# BatteryV8.net
KiCad netlist of a schematic drawn in EAGLE
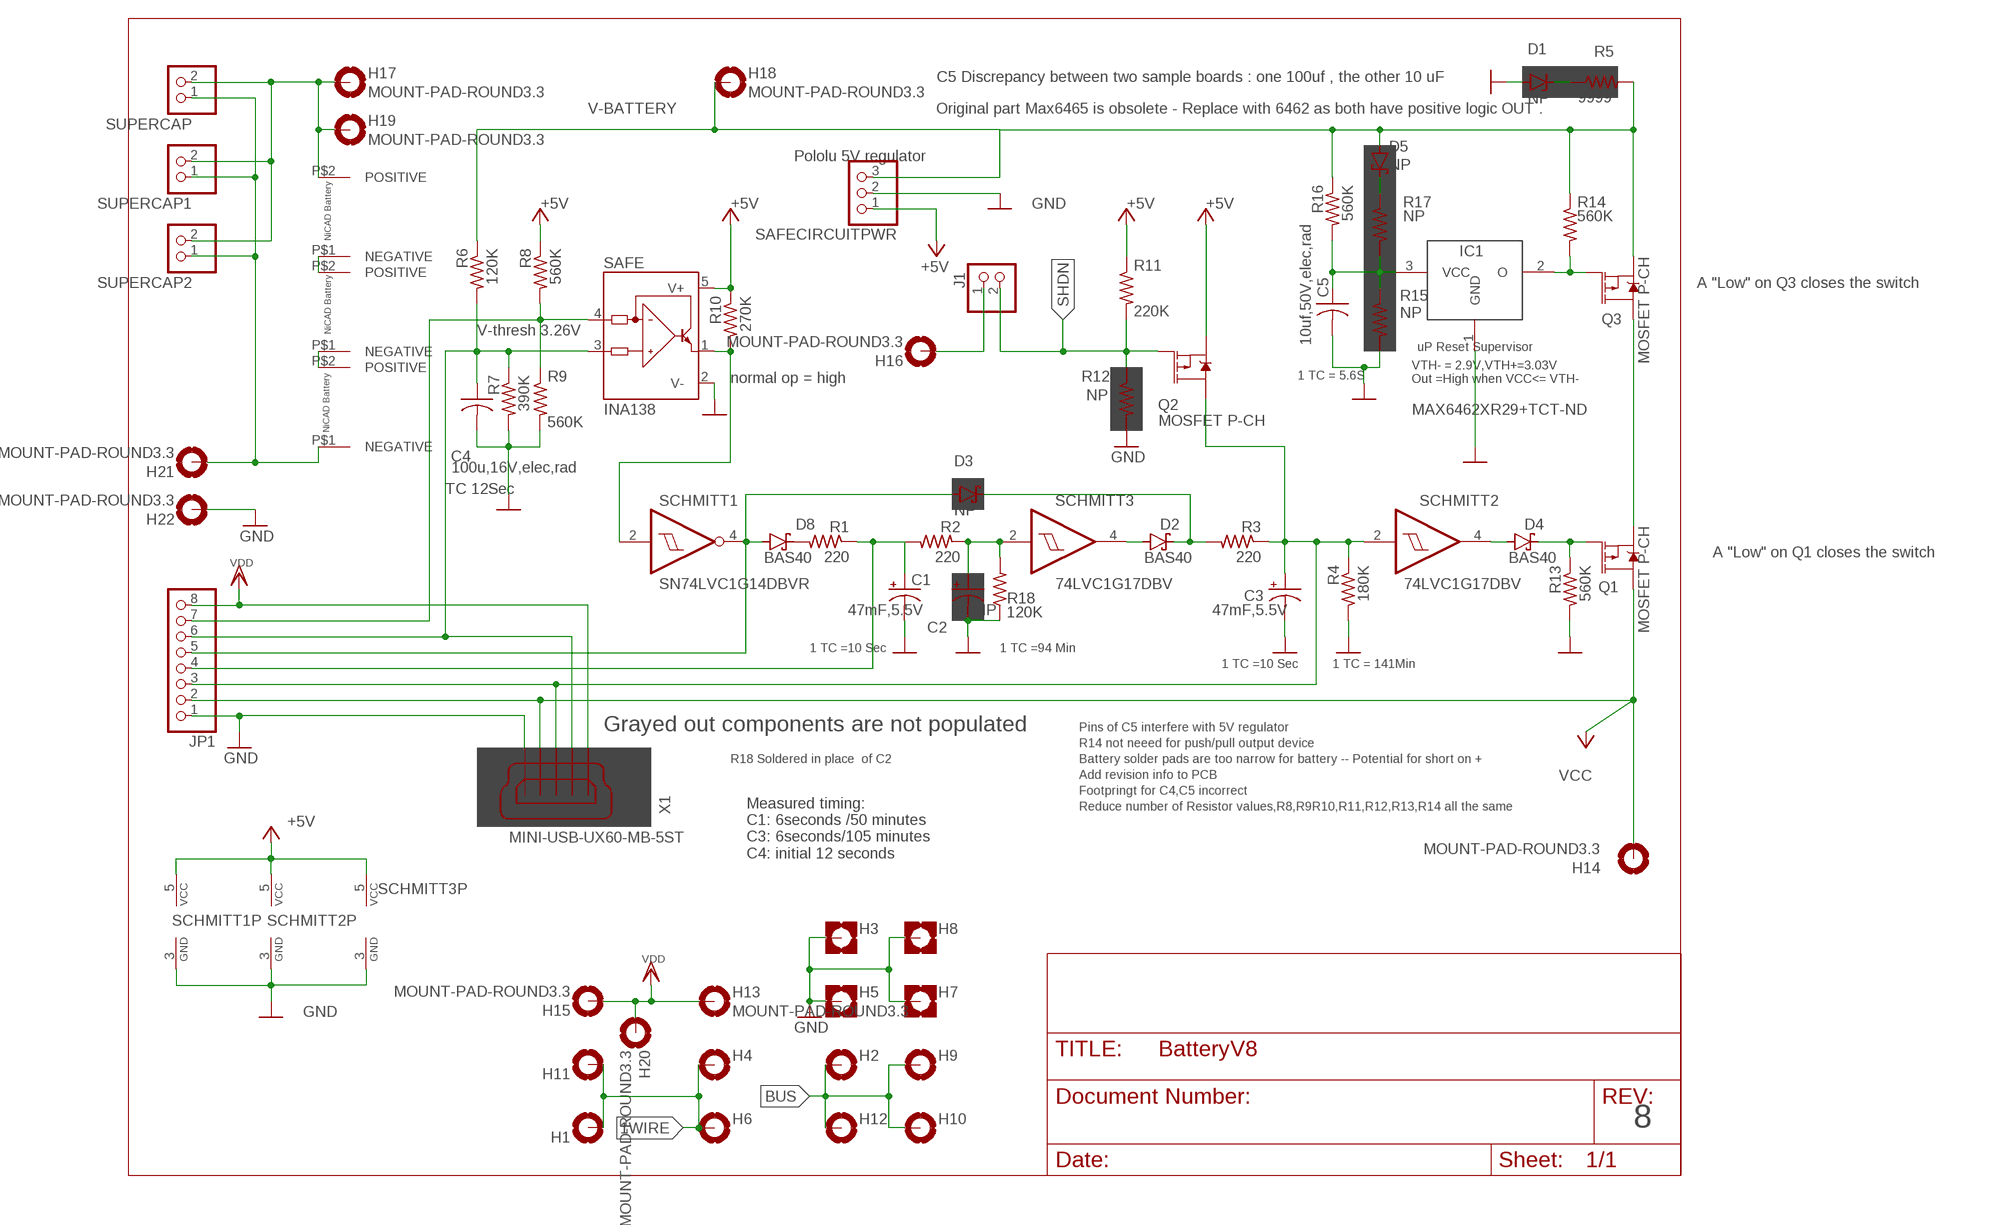
[diagram p0: schematic, sheet 1]

(export (version "E")
  (design (tool "Eeschema 10.0.6"))
  (components
    (comp (ref "C1")
      (value "47mF,5.5V")
      (footprint "eagle-import:153CLV-1010")
      (libsource (lib "eagle-import") (part "CPOL-US153CLV-1010"))
    )
    (comp (ref "C2")
      (value "NP")
      (footprint "eagle-import:153CLV-1010")
      (libsource (lib "eagle-import") (part "CPOL-US153CLV-1010"))
    )
    (comp (ref "C3")
      (value "47mF,5.5V")
      (footprint "eagle-import:153CLV-1010")
      (libsource (lib "eagle-import") (part "CPOL-US153CLV-1010"))
    )
    (comp (ref "C4")
      (value "100u,16V,elec,rad")
      (footprint "eagle-import:C050-030X075")
      (libsource (lib "eagle-import") (part "C-US050-030X075"))
    )
    (comp (ref "C5")
      (value "10uf,50V,elec,rad")
      (footprint "eagle-import:C050-030X075")
      (libsource (lib "eagle-import") (part "C-US050-030X075"))
    )
    (comp (ref "D1")
      (value "NP")
      (footprint "eagle-import:DO35Z10")
      (libsource (lib "eagle-import") (part "1N821"))
    )
    (comp (ref "D2")
      (value "BAS40")
      (footprint "eagle-import:SOT23")
      (libsource (lib "eagle-import") (part "BAS40"))
    )
    (comp (ref "D3")
      (value "NP")
      (footprint "eagle-import:SOT23")
      (libsource (lib "eagle-import") (part "BAS40"))
    )
    (comp (ref "D4")
      (value "BAS40")
      (footprint "eagle-import:SOT23")
      (libsource (lib "eagle-import") (part "BAS40"))
    )
    (comp (ref "D5")
      (value "NP")
      (footprint "eagle-import:SOT23")
      (libsource (lib "eagle-import") (part "BAS40"))
    )
    (comp (ref "D8")
      (value "BAS40")
      (footprint "eagle-import:SOT23")
      (libsource (lib "eagle-import") (part "BAS40"))
    )
    (comp (ref "H1")
      (value "MOUNT-PAD-ROUND3.3")
      (footprint "eagle-import:3,3-PAD")
      (libsource (lib "eagle-import") (part "MOUNT-PAD-ROUND3.3"))
    )
    (comp (ref "H2")
      (value "MOUNT-PAD-ROUND3.3")
      (footprint "eagle-import:3,3-PAD")
      (libsource (lib "eagle-import") (part "MOUNT-PAD-ROUND3.3"))
    )
    (comp (ref "H3")
      (value "MOUNT-PAD-SQUARE3.3")
      (footprint "eagle-import:3,3-PAD-SQUARE")
      (libsource (lib "eagle-import") (part "MOUNT-PAD-SQUARE3.3"))
    )
    (comp (ref "H4")
      (value "MOUNT-PAD-ROUND3.3")
      (footprint "eagle-import:3,3-PAD")
      (libsource (lib "eagle-import") (part "MOUNT-PAD-ROUND3.3"))
    )
    (comp (ref "H5")
      (value "MOUNT-PAD-SQUARE3.3")
      (footprint "eagle-import:3,3-PAD-SQUARE")
      (libsource (lib "eagle-import") (part "MOUNT-PAD-SQUARE3.3"))
    )
    (comp (ref "H6")
      (value "MOUNT-PAD-ROUND3.3")
      (footprint "eagle-import:3,3-PAD")
      (libsource (lib "eagle-import") (part "MOUNT-PAD-ROUND3.3"))
    )
    (comp (ref "H7")
      (value "MOUNT-PAD-SQUARE3.3")
      (footprint "eagle-import:3,3-PAD-SQUARE")
      (libsource (lib "eagle-import") (part "MOUNT-PAD-SQUARE3.3"))
    )
    (comp (ref "H8")
      (value "MOUNT-PAD-SQUARE3.3")
      (footprint "eagle-import:3,3-PAD-SQUARE")
      (libsource (lib "eagle-import") (part "MOUNT-PAD-SQUARE3.3"))
    )
    (comp (ref "H9")
      (value "MOUNT-PAD-ROUND3.3")
      (footprint "eagle-import:3,3-PAD")
      (libsource (lib "eagle-import") (part "MOUNT-PAD-ROUND3.3"))
    )
    (comp (ref "H10")
      (value "MOUNT-PAD-ROUND3.3")
      (footprint "eagle-import:3,3-PAD")
      (libsource (lib "eagle-import") (part "MOUNT-PAD-ROUND3.3"))
    )
    (comp (ref "H11")
      (value "MOUNT-PAD-ROUND3.3")
      (footprint "eagle-import:3,3-PAD")
      (libsource (lib "eagle-import") (part "MOUNT-PAD-ROUND3.3"))
    )
    (comp (ref "H12")
      (value "MOUNT-PAD-ROUND3.3")
      (footprint "eagle-import:3,3-PAD")
      (libsource (lib "eagle-import") (part "MOUNT-PAD-ROUND3.3"))
    )
    (comp (ref "H13")
      (value "MOUNT-PAD-ROUND3.3")
      (footprint "eagle-import:3,3-PAD")
      (libsource (lib "eagle-import") (part "MOUNT-PAD-ROUND3.3"))
    )
    (comp (ref "H14")
      (value "MOUNT-PAD-ROUND3.3")
      (footprint "eagle-import:3,3-PAD")
      (libsource (lib "eagle-import") (part "MOUNT-PAD-ROUND3.3"))
    )
    (comp (ref "H15")
      (value "MOUNT-PAD-ROUND3.3")
      (footprint "eagle-import:3,3-PAD")
      (libsource (lib "eagle-import") (part "MOUNT-PAD-ROUND3.3"))
    )
    (comp (ref "H16")
      (value "MOUNT-PAD-ROUND3.3")
      (footprint "eagle-import:3,3-PAD")
      (libsource (lib "eagle-import") (part "MOUNT-PAD-ROUND3.3"))
    )
    (comp (ref "H17")
      (value "MOUNT-PAD-ROUND3.3")
      (footprint "eagle-import:3,3-PAD")
      (libsource (lib "eagle-import") (part "MOUNT-PAD-ROUND3.3"))
    )
    (comp (ref "H18")
      (value "MOUNT-PAD-ROUND3.3")
      (footprint "eagle-import:3,3-PAD")
      (libsource (lib "eagle-import") (part "MOUNT-PAD-ROUND3.3"))
    )
    (comp (ref "H19")
      (value "MOUNT-PAD-ROUND3.3")
      (footprint "eagle-import:3,3-PAD")
      (libsource (lib "eagle-import") (part "MOUNT-PAD-ROUND3.3"))
    )
    (comp (ref "H20")
      (value "MOUNT-PAD-ROUND3.3")
      (footprint "eagle-import:3,3-PAD")
      (libsource (lib "eagle-import") (part "MOUNT-PAD-ROUND3.3"))
    )
    (comp (ref "H21")
      (value "MOUNT-PAD-ROUND3.3")
      (footprint "eagle-import:3,3-PAD")
      (libsource (lib "eagle-import") (part "MOUNT-PAD-ROUND3.3"))
    )
    (comp (ref "H22")
      (value "MOUNT-PAD-ROUND3.3")
      (footprint "eagle-import:3,3-PAD")
      (libsource (lib "eagle-import") (part "MOUNT-PAD-ROUND3.3"))
    )
    (comp (ref "IC1")
      (value "MAX6462XR29T")
      (footprint "eagle-import:EDGECUBE_SC70-3")
      (fields (field (name "DIGIKEY") "MAX6462XR29+TCT-ND"))
      (libsource (lib "eagle-import") (part "EDGECUBE_MAX6465"))
    )
    (comp (ref "J1")
      (value "PINHD-1X2")
      (footprint "eagle-import:1X02")
      (libsource (lib "eagle-import") (part "PINHD-1X2"))
    )
    (comp (ref "JP1")
      (value "PINHD-1X8")
      (footprint "eagle-import:1X08")
      (libsource (lib "eagle-import") (part "PINHD-1X8"))
    )
    (comp (ref "Q1")
      (value "MOSFET P-CH")
      (footprint "eagle-import:SOT23-3")
      (libsource (lib "eagle-import") (part "MOSFET_PCH-SI2309DS"))
    )
    (comp (ref "Q2")
      (value "MOSFET P-CH")
      (footprint "eagle-import:SOT23-3")
      (libsource (lib "eagle-import") (part "MOSFET_PCH-SI2309DS"))
    )
    (comp (ref "Q3")
      (value "MOSFET P-CH")
      (footprint "eagle-import:SOT23-3")
      (libsource (lib "eagle-import") (part "MOSFET_PCH-SI2309DS"))
    )
    (comp (ref "R1")
      (value "220")
      (footprint "eagle-import:R0805")
      (libsource (lib "eagle-import") (part "R-US_R0805"))
    )
    (comp (ref "R2")
      (value "220")
      (footprint "eagle-import:R0805")
      (libsource (lib "eagle-import") (part "R-US_R0805"))
    )
    (comp (ref "R3")
      (value "220")
      (footprint "eagle-import:R0805")
      (libsource (lib "eagle-import") (part "R-US_R0805"))
    )
    (comp (ref "R4")
      (value "180K")
      (footprint "eagle-import:R0805")
      (libsource (lib "eagle-import") (part "R-US_R0805"))
    )
    (comp (ref "R5")
      (value "9999")
      (footprint "eagle-import:0207_10")
      (libsource (lib "eagle-import") (part "R-US_0207/10"))
    )
    (comp (ref "R6")
      (value "120K")
      (footprint "eagle-import:R0805")
      (libsource (lib "eagle-import") (part "R-US_R0805"))
    )
    (comp (ref "R7")
      (value "390K")
      (footprint "eagle-import:R0805")
      (libsource (lib "eagle-import") (part "R-US_R0805"))
    )
    (comp (ref "R8")
      (value "560K")
      (footprint "eagle-import:R0805")
      (libsource (lib "eagle-import") (part "R-US_R0805"))
    )
    (comp (ref "R9")
      (value "560K")
      (footprint "eagle-import:R0805")
      (libsource (lib "eagle-import") (part "R-US_R0805"))
    )
    (comp (ref "R10")
      (value "270K")
      (footprint "eagle-import:R0805")
      (libsource (lib "eagle-import") (part "R-US_R0805"))
    )
    (comp (ref "R11")
      (value "220K")
      (footprint "eagle-import:R0805")
      (libsource (lib "eagle-import") (part "R-US_R0805"))
    )
    (comp (ref "R12")
      (value "NP")
      (footprint "eagle-import:R0805")
      (libsource (lib "eagle-import") (part "R-US_R0805"))
    )
    (comp (ref "R13")
      (value "560K")
      (footprint "eagle-import:R0805")
      (libsource (lib "eagle-import") (part "R-US_R0805"))
    )
    (comp (ref "R14")
      (value "560K")
      (footprint "eagle-import:R0805")
      (libsource (lib "eagle-import") (part "R-US_R0805"))
    )
    (comp (ref "R15")
      (value "NP")
      (footprint "eagle-import:R0805")
      (libsource (lib "eagle-import") (part "R-US_R0805"))
    )
    (comp (ref "R16")
      (value "560K")
      (footprint "eagle-import:R0805")
      (libsource (lib "eagle-import") (part "R-US_R0805"))
    )
    (comp (ref "R17")
      (value "NP")
      (footprint "eagle-import:R0805")
      (libsource (lib "eagle-import") (part "R-US_R0805"))
    )
    (comp (ref "R18")
      (value "120K")
      (footprint "eagle-import:R0805")
      (libsource (lib "eagle-import") (part "R-US_R0805"))
    )
    (comp (ref "SAFE")
      (value "INA138")
      (footprint "eagle-import:SOT23-5")
      (fields (field (name "MF") "TEXAS INSTRUMENTS") (field (name "MPN") "INA138NA/250"))
      (libsource (lib "eagle-import") (part "INA138"))
    )
    (comp (ref "SAFECIRCUITPWR")
      (value "PINHD-1X3")
      (footprint "eagle-import:1X03")
      (libsource (lib "eagle-import") (part "PINHD-1X3"))
    )
    (comp (ref "SCHMITT1")
      (value "SN74LVC1G14DBVR")
      (footprint "eagle-import:SOT23-5")
      (fields (field (name "DIGIKET") "296-11607-1-ND") (field (name "TOPMARK") "U14F,U14R"))
      (libsource (lib "eagle-import") (part "741G14DBVAUC"))
    )
    (comp (ref "SCHMITT2")
      (value "74LVC1G17DBV")
      (footprint "eagle-import:SOT23-5")
      (fields (field (name "DIGIKEY") "296-11933-1-ND") (field (name "TOPMARK") "C175"))
      (libsource (lib "eagle-import") (part "741G17DBVLVC"))
    )
    (comp (ref "SCHMITT3")
      (value "74LVC1G17DBV")
      (footprint "eagle-import:SOT23-5")
      (fields (field (name "DIGIKEY") "296-11933-1-ND") (field (name "TOPMARK") "C175"))
      (libsource (lib "eagle-import") (part "741G17DBVLVC"))
    )
    (comp (ref "SUPERCAP")
      (value "PINHD-1X2")
      (footprint "eagle-import:1X02")
      (libsource (lib "eagle-import") (part "PINHD-1X2"))
    )
    (comp (ref "SUPERCAP1")
      (value "PINHD-1X2")
      (footprint "eagle-import:1X02")
      (libsource (lib "eagle-import") (part "PINHD-1X2"))
    )
    (comp (ref "SUPERCAP2")
      (value "PINHD-1X2")
      (footprint "eagle-import:1X02")
      (libsource (lib "eagle-import") (part "PINHD-1X2"))
    )
    (comp (ref "U$5")
      (value "JST-WATCH_AA-BATT")
      (footprint "eagle-import:JST-WATCH_AA-BATT")
      (libsource (lib "eagle-import") (part "JST-WATCH_AA-BATT"))
    )
    (comp (ref "U$6")
      (value "JST-WATCH_AA-BATT")
      (footprint "eagle-import:JST-WATCH_AA-BATT")
      (libsource (lib "eagle-import") (part "JST-WATCH_AA-BATT"))
    )
    (comp (ref "U$7")
      (value "JST-WATCH_AA-BATT")
      (footprint "eagle-import:JST-WATCH_AA-BATT")
      (libsource (lib "eagle-import") (part "JST-WATCH_AA-BATT"))
    )
    (comp (ref "X1")
      (value "MINI-USB-UX60-MB-5ST")
      (footprint "eagle-import:UX60-MB-5ST")
      (libsource (lib "eagle-import") (part "MINI-USB-UX60-MB-5ST"))
    )
  )
  (nets
    (net (code "1") (name "+3V3") (class "Default")
      (node (ref "Q2") (pin "2") (pinfunction "S_2") (pintype "bidirectional"))
      (node (ref "R10") (pin "1") (pinfunction "1_1") (pintype "passive"))
      (node (ref "R11") (pin "1") (pinfunction "1_1") (pintype "passive"))
      (node (ref "R8") (pin "1") (pinfunction "1_1") (pintype "passive"))
      (node (ref "SAFE") (pin "5") (pinfunction "V+_5") (pintype "power_in"))
      (node (ref "SAFECIRCUITPWR") (pin "1") (pinfunction "1_1") (pintype "passive"))
      (node (ref "SCHMITT1") (pin "5") (pinfunction "VCC_5") (pintype "power_in"))
      (node (ref "SCHMITT2") (pin "5") (pinfunction "VCC_5") (pintype "power_in"))
      (node (ref "SCHMITT3") (pin "5") (pinfunction "VCC_5") (pintype "power_in"))
    )
    (net (code "2") (name "/V-BATTERY") (class "Default")
      (node (ref "D5") (pin "1") (pinfunction "A_1") (pintype "passive"))
      (node (ref "H18") (pin "B3,3") (pinfunction "MOUNT_B3,3") (pintype "passive"))
      (node (ref "Q3") (pin "2") (pinfunction "S_2") (pintype "bidirectional"))
      (node (ref "R14") (pin "1") (pinfunction "1_1") (pintype "passive"))
      (node (ref "R16") (pin "1") (pinfunction "1_1") (pintype "passive"))
      (node (ref "R5") (pin "2") (pinfunction "2_2") (pintype "passive"))
      (node (ref "R6") (pin "1") (pinfunction "1_1") (pintype "passive"))
      (node (ref "SAFECIRCUITPWR") (pin "3") (pinfunction "3_3") (pintype "passive"))
    )
    (net (code "3") (name "1WIRE") (class "Default")
      (node (ref "H1") (pin "B3,3") (pinfunction "MOUNT_B3,3") (pintype "passive"))
      (node (ref "H11") (pin "B3,3") (pinfunction "MOUNT_B3,3") (pintype "passive"))
      (node (ref "H4") (pin "B3,3") (pinfunction "MOUNT_B3,3") (pintype "passive"))
      (node (ref "H6") (pin "B3,3") (pinfunction "MOUNT_B3,3") (pintype "passive"))
    )
    (net (code "4") (name "BUS") (class "Default")
      (node (ref "H10") (pin "B3,3") (pinfunction "MOUNT_B3,3") (pintype "passive"))
      (node (ref "H12") (pin "B3,3") (pinfunction "MOUNT_B3,3") (pintype "passive"))
      (node (ref "H2") (pin "B3,3") (pinfunction "MOUNT_B3,3") (pintype "passive"))
      (node (ref "H9") (pin "B3,3") (pinfunction "MOUNT_B3,3") (pintype "passive"))
    )
    (net (code "5") (name "GND") (class "Default")
      (node (ref "C1") (pin "-") (pinfunction "-_-") (pintype "passive"))
      (node (ref "C2") (pin "-") (pinfunction "-_-") (pintype "passive"))
      (node (ref "C3") (pin "-") (pinfunction "-_-") (pintype "passive"))
      (node (ref "C4") (pin "2") (pinfunction "2_2") (pintype "passive"))
      (node (ref "C5") (pin "2") (pinfunction "2_2") (pintype "passive"))
      (node (ref "D1") (pin "A") (pinfunction "A_A") (pintype "passive"))
      (node (ref "H22") (pin "B3,3") (pinfunction "MOUNT_B3,3") (pintype "passive"))
      (node (ref "H3") (pin "B3,3") (pinfunction "MOUNT_B3,3") (pintype "passive"))
      (node (ref "H5") (pin "B3,3") (pinfunction "MOUNT_B3,3") (pintype "passive"))
      (node (ref "H7") (pin "B3,3") (pinfunction "MOUNT_B3,3") (pintype "passive"))
      (node (ref "H8") (pin "B3,3") (pinfunction "MOUNT_B3,3") (pintype "passive"))
      (node (ref "IC1") (pin "1") (pinfunction "GND_1") (pintype "bidirectional"))
      (node (ref "JP1") (pin "1") (pinfunction "1_1") (pintype "passive"))
      (node (ref "R12") (pin "2") (pinfunction "2_2") (pintype "passive"))
      (node (ref "R13") (pin "2") (pinfunction "2_2") (pintype "passive"))
      (node (ref "R15") (pin "2") (pinfunction "2_2") (pintype "passive"))
      (node (ref "R18") (pin "1") (pinfunction "1_1") (pintype "passive"))
      (node (ref "R4") (pin "2") (pinfunction "2_2") (pintype "passive"))
      (node (ref "R7") (pin "2") (pinfunction "2_2") (pintype "passive"))
      (node (ref "R9") (pin "2") (pinfunction "2_2") (pintype "passive"))
      (node (ref "SAFE") (pin "2") (pinfunction "V-_2") (pintype "power_in"))
      (node (ref "SAFECIRCUITPWR") (pin "2") (pinfunction "2_2") (pintype "passive"))
      (node (ref "SCHMITT1") (pin "3") (pinfunction "GND_3") (pintype "power_in"))
      (node (ref "SCHMITT2") (pin "3") (pinfunction "GND_3") (pintype "power_in"))
      (node (ref "SCHMITT3") (pin "3") (pinfunction "GND_3") (pintype "power_in"))
      (node (ref "X1") (pin "5") (pinfunction "5_5") (pintype "input"))
    )
    (net (code "6") (name "Net-(C1-Pad+)") (class "Default")
      (node (ref "C1") (pin "+") (pinfunction "+_+") (pintype "passive"))
      (node (ref "JP1") (pin "4") (pinfunction "4_4") (pintype "passive"))
      (node (ref "R1") (pin "1") (pinfunction "1_1") (pintype "passive"))
      (node (ref "R2") (pin "2") (pinfunction "2_2") (pintype "passive"))
    )
    (net (code "7") (name "Net-(D1-PadC)") (class "Default")
      (node (ref "D1") (pin "C") (pinfunction "C_C") (pintype "passive"))
      (node (ref "R5") (pin "1") (pinfunction "1_1") (pintype "passive"))
    )
    (net (code "8") (name "Net-(D2-A)") (class "Default")
      (node (ref "D2") (pin "1") (pinfunction "A_1") (pintype "passive"))
      (node (ref "SCHMITT3") (pin "4") (pinfunction "O_4") (pintype "output"))
    )
    (net (code "9") (name "Net-(D2-C)") (class "Default")
      (node (ref "D2") (pin "3") (pinfunction "C_3") (pintype "passive"))
      (node (ref "D3") (pin "3") (pinfunction "C_3") (pintype "passive"))
      (node (ref "R3") (pin "2") (pinfunction "2_2") (pintype "passive"))
    )
    (net (code "10") (name "Net-(D3-A)") (class "Default")
      (node (ref "D3") (pin "1") (pinfunction "A_1") (pintype "passive"))
      (node (ref "D8") (pin "1") (pinfunction "A_1") (pintype "passive"))
      (node (ref "JP1") (pin "5") (pinfunction "5_5") (pintype "passive"))
      (node (ref "SCHMITT1") (pin "4") (pinfunction "O_4") (pintype "output"))
    )
    (net (code "11") (name "Net-(D4-A)") (class "Default")
      (node (ref "D4") (pin "1") (pinfunction "A_1") (pintype "passive"))
      (node (ref "SCHMITT2") (pin "4") (pinfunction "O_4") (pintype "output"))
    )
    (net (code "12") (name "Net-(D4-C)") (class "Default")
      (node (ref "D4") (pin "3") (pinfunction "C_3") (pintype "passive"))
      (node (ref "Q1") (pin "1") (pinfunction "G_1") (pintype "bidirectional"))
      (node (ref "R13") (pin "1") (pinfunction "1_1") (pintype "passive"))
    )
    (net (code "13") (name "Net-(D5-C)") (class "Default")
      (node (ref "D5") (pin "3") (pinfunction "C_3") (pintype "passive"))
      (node (ref "R17") (pin "1") (pinfunction "1_1") (pintype "passive"))
    )
    (net (code "14") (name "Net-(D8-C)") (class "Default")
      (node (ref "D8") (pin "3") (pinfunction "C_3") (pintype "passive"))
      (node (ref "R1") (pin "2") (pinfunction "2_2") (pintype "passive"))
    )
    (net (code "15") (name "Net-(H16-MOUNT)") (class "Default")
      (node (ref "H16") (pin "B3,3") (pinfunction "MOUNT_B3,3") (pintype "passive"))
      (node (ref "J1") (pin "1") (pinfunction "1_1") (pintype "passive"))
    )
    (net (code "16") (name "Net-(H17-MOUNT)") (class "Default")
      (node (ref "H17") (pin "B3,3") (pinfunction "MOUNT_B3,3") (pintype "passive"))
      (node (ref "H19") (pin "B3,3") (pinfunction "MOUNT_B3,3") (pintype "passive"))
      (node (ref "SUPERCAP") (pin "2") (pinfunction "2_2") (pintype "passive"))
      (node (ref "SUPERCAP1") (pin "2") (pinfunction "2_2") (pintype "passive"))
      (node (ref "SUPERCAP2") (pin "2") (pinfunction "2_2") (pintype "passive"))
      (node (ref "U$7") (pin "P$2") (pinfunction "POSITIVE_P$2") (pintype "bidirectional"))
    )
    (net (code "17") (name "Net-(H21-MOUNT)") (class "Default")
      (node (ref "H21") (pin "B3,3") (pinfunction "MOUNT_B3,3") (pintype "passive"))
      (node (ref "SUPERCAP") (pin "1") (pinfunction "1_1") (pintype "passive"))
      (node (ref "SUPERCAP1") (pin "1") (pinfunction "1_1") (pintype "passive"))
      (node (ref "SUPERCAP2") (pin "1") (pinfunction "1_1") (pintype "passive"))
      (node (ref "U$5") (pin "P$1") (pinfunction "NEGATIVE_P$1") (pintype "bidirectional"))
    )
    (net (code "18") (name "Net-(IC1-O)") (class "Default")
      (node (ref "IC1") (pin "2") (pinfunction "O_2") (pintype "bidirectional"))
      (node (ref "Q3") (pin "1") (pinfunction "G_1") (pintype "bidirectional"))
      (node (ref "R14") (pin "2") (pinfunction "2_2") (pintype "passive"))
    )
    (net (code "19") (name "Net-(IC1-VCC)") (class "Default")
      (node (ref "C5") (pin "1") (pinfunction "1_1") (pintype "passive"))
      (node (ref "IC1") (pin "3") (pinfunction "VCC_3") (pintype "bidirectional"))
      (node (ref "R15") (pin "1") (pinfunction "1_1") (pintype "passive"))
      (node (ref "R16") (pin "2") (pinfunction "2_2") (pintype "passive"))
      (node (ref "R17") (pin "2") (pinfunction "2_2") (pintype "passive"))
    )
    (net (code "20") (name "Net-(Q1-S)") (class "Default")
      (node (ref "Q1") (pin "2") (pinfunction "S_2") (pintype "bidirectional"))
      (node (ref "Q3") (pin "3") (pinfunction "D_3") (pintype "bidirectional"))
    )
    (net (code "21") (name "Net-(Q2-D)") (class "Default")
      (node (ref "C3") (pin "+") (pinfunction "+_+") (pintype "passive"))
      (node (ref "JP1") (pin "3") (pinfunction "3_3") (pintype "passive"))
      (node (ref "Q2") (pin "3") (pinfunction "D_3") (pintype "bidirectional"))
      (node (ref "R3") (pin "1") (pinfunction "1_1") (pintype "passive"))
      (node (ref "R4") (pin "1") (pinfunction "1_1") (pintype "passive"))
      (node (ref "SCHMITT2") (pin "2") (pinfunction "I_2") (pintype "input"))
      (node (ref "X1") (pin "3") (pinfunction "3_3") (pintype "input"))
    )
    (net (code "22") (name "Net-(SAFE-IN+)") (class "Default")
      (node (ref "C4") (pin "1") (pinfunction "1_1") (pintype "passive"))
      (node (ref "JP1") (pin "6") (pinfunction "6_6") (pintype "passive"))
      (node (ref "R6") (pin "2") (pinfunction "2_2") (pintype "passive"))
      (node (ref "R7") (pin "1") (pinfunction "1_1") (pintype "passive"))
      (node (ref "SAFE") (pin "3") (pinfunction "IN+_3") (pintype "input"))
      (node (ref "X1") (pin "2") (pinfunction "2_2") (pintype "input"))
    )
    (net (code "23") (name "Net-(SAFE-IN-)") (class "Default")
      (node (ref "JP1") (pin "7") (pinfunction "7_7") (pintype "passive"))
      (node (ref "R8") (pin "2") (pinfunction "2_2") (pintype "passive"))
      (node (ref "R9") (pin "1") (pinfunction "1_1") (pintype "passive"))
      (node (ref "SAFE") (pin "4") (pinfunction "IN-_4") (pintype "input"))
    )
    (net (code "24") (name "Net-(SAFE-OUT)") (class "Default")
      (node (ref "R10") (pin "2") (pinfunction "2_2") (pintype "passive"))
      (node (ref "SAFE") (pin "1") (pinfunction "OUT_1") (pintype "output"))
      (node (ref "SCHMITT1") (pin "2") (pinfunction "I_2") (pintype "input"))
    )
    (net (code "25") (name "Net-(SCHMITT3A-I)") (class "Default")
      (node (ref "C2") (pin "+") (pinfunction "+_+") (pintype "passive"))
      (node (ref "R18") (pin "2") (pinfunction "2_2") (pintype "passive"))
      (node (ref "R2") (pin "1") (pinfunction "1_1") (pintype "passive"))
      (node (ref "SCHMITT3") (pin "2") (pinfunction "I_2") (pintype "input"))
    )
    (net (code "26") (name "Net-(U$5-POSITIVE)") (class "Default")
      (node (ref "U$5") (pin "P$2") (pinfunction "POSITIVE_P$2") (pintype "bidirectional"))
      (node (ref "U$6") (pin "P$1") (pinfunction "NEGATIVE_P$1") (pintype "bidirectional"))
    )
    (net (code "27") (name "Net-(U$6-POSITIVE)") (class "Default")
      (node (ref "U$6") (pin "P$2") (pinfunction "POSITIVE_P$2") (pintype "bidirectional"))
      (node (ref "U$7") (pin "P$1") (pinfunction "NEGATIVE_P$1") (pintype "bidirectional"))
    )
    (net (code "28") (name "SHDN") (class "Default")
      (node (ref "J1") (pin "2") (pinfunction "2_2") (pintype "passive"))
      (node (ref "Q2") (pin "1") (pinfunction "G_1") (pintype "bidirectional"))
      (node (ref "R11") (pin "2") (pinfunction "2_2") (pintype "passive"))
      (node (ref "R12") (pin "1") (pinfunction "1_1") (pintype "passive"))
    )
    (net (code "29") (name "VCC") (class "Default")
      (node (ref "H14") (pin "B3,3") (pinfunction "MOUNT_B3,3") (pintype "passive"))
      (node (ref "JP1") (pin "2") (pinfunction "2_2") (pintype "passive"))
      (node (ref "Q1") (pin "3") (pinfunction "D_3") (pintype "bidirectional"))
      (node (ref "X1") (pin "4") (pinfunction "4_4") (pintype "input"))
    )
    (net (code "30") (name "VDD") (class "Default")
      (node (ref "H13") (pin "B3,3") (pinfunction "MOUNT_B3,3") (pintype "passive"))
      (node (ref "H15") (pin "B3,3") (pinfunction "MOUNT_B3,3") (pintype "passive"))
      (node (ref "H20") (pin "B3,3") (pinfunction "MOUNT_B3,3") (pintype "passive"))
      (node (ref "JP1") (pin "8") (pinfunction "8_8") (pintype "passive"))
      (node (ref "X1") (pin "1") (pinfunction "1_1") (pintype "input"))
    )
  )
)
